# Main.net
KiCad netlist of a schematic drawn in Altium Designer
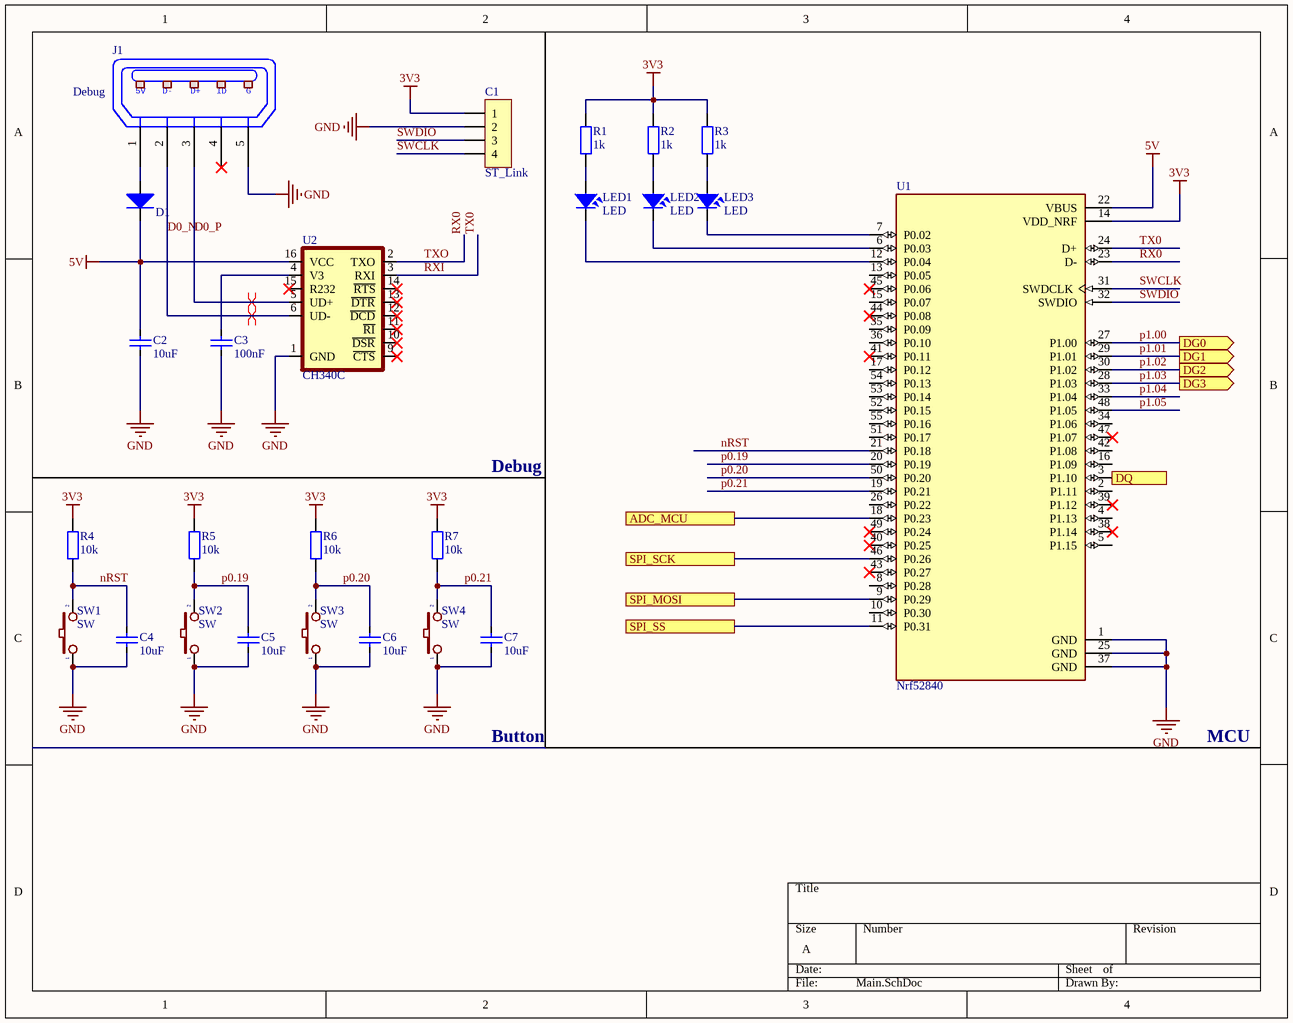
[diagram p0: Main.SchDoc]

(export (version "E")
  (design (tool "Eeschema 10.0.6"))
  (components
    (comp (ref "C1")
      (value "ST_Link")
      (footprint "J4-D1T")
      (description "WR-PHD 2.00 mm Socket Header")
      (fields
        (field (name "MANUFACTURER") "Würth Elektronik eiSos GmbH")
        (field (name "PARTNO") "62000411821")
        (field (name "CREATED BY") "Karrer Zheng")
      )
      (libsource (lib "Main") (part "JP4x1-2.0"))
    )
    (comp (ref "C2")
      (value "10uF")
      (footprint "CAP_0805")
      (description "Capacitor")
      (fields (field (name "PUBLISHER") "Altium Limited"))
      (libsource (lib "My Library") (part "CapSMD"))
    )
    (comp (ref "C3")
      (value "100nF")
      (footprint "CAP_0805")
      (description "Capacitor")
      (fields (field (name "PUBLISHER") "Altium Limited"))
      (libsource (lib "My Library") (part "CapSMD"))
    )
    (comp (ref "C4")
      (value "10uF")
      (footprint "CAP_0805")
      (description "Capacitor")
      (fields (field (name "PUBLISHER") "Altium Limited"))
      (libsource (lib "My Library") (part "CapSMD"))
    )
    (comp (ref "C5")
      (value "10uF")
      (footprint "CAP_0805")
      (description "Capacitor")
      (fields (field (name "PUBLISHER") "Altium Limited"))
      (libsource (lib "My Library") (part "CapSMD"))
    )
    (comp (ref "C6")
      (value "10uF")
      (footprint "CAP_0805")
      (description "Capacitor")
      (fields (field (name "PUBLISHER") "Altium Limited"))
      (libsource (lib "My Library") (part "CapSMD"))
    )
    (comp (ref "C7")
      (value "10uF")
      (footprint "CAP_0805")
      (description "Capacitor")
      (fields (field (name "PUBLISHER") "Altium Limited"))
      (libsource (lib "My Library") (part "CapSMD"))
    )
    (comp (ref "D1")
      (value "Diode SMD")
      (footprint "DIO-214AC(SMA)")
      (description "Default Diode")
      (fields (field (name "PUBLISHER") "Altium Limited"))
      (libsource (lib "My Library") (part "Diode SMD"))
    )
    (comp (ref "J1")
      (value "Debug")
      (footprint "USB-M1")
      (fields
        (field (name "MANUFACTURER") "FCI")
        (field (name "MANUFACTURER PART NUMBER") "10118193-0001LF")
        (field (name ".CREATOR") "MM")
        (field (name ".CHECKED PCB") "RF")
        (field (name ".CHECKED SCH") "MM")
      )
      (libsource (lib "My Library") (part "USB-5"))
    )
    (comp (ref "LED1")
      (value "LED")
      (footprint "LED-0805-Red")
      (description "LED Single colour Green and Red")
      (libsource (lib "My Library") (part "LED"))
    )
    (comp (ref "LED2")
      (value "LED")
      (footprint "LED-0805-Yellow")
      (description "LED Single colour Green and Red")
      (libsource (lib "My Library") (part "LED"))
    )
    (comp (ref "LED3")
      (value "LED")
      (footprint "LED-0805-Green")
      (description "LED Single colour Green and Red")
      (libsource (lib "My Library") (part "LED"))
    )
    (comp (ref "R1")
      (value "1k")
      (footprint "RES-SMD-0805")
      (description "Resistor SMD")
      (fields
        (field (name "MANUFACTURER") "Generic Components")
        (field (name "PUBLISHER") "Altium Hobart Technology Centre")
      )
      (libsource (lib "My Library") (part "Resistor - SMD"))
    )
    (comp (ref "R2")
      (value "1k")
      (footprint "RES-SMD-0805")
      (description "Resistor SMD")
      (fields
        (field (name "MANUFACTURER") "Generic Components")
        (field (name "PUBLISHER") "Altium Hobart Technology Centre")
      )
      (libsource (lib "My Library") (part "Resistor - SMD"))
    )
    (comp (ref "R3")
      (value "1k")
      (footprint "RES-SMD-0805")
      (description "Resistor SMD")
      (fields
        (field (name "MANUFACTURER") "Generic Components")
        (field (name "PUBLISHER") "Altium Hobart Technology Centre")
      )
      (libsource (lib "My Library") (part "Resistor - SMD"))
    )
    (comp (ref "R4")
      (value "10k")
      (footprint "RES-SMD-0805")
      (description "Resistor SMD")
      (fields
        (field (name "MANUFACTURER") "Generic Components")
        (field (name "PUBLISHER") "Altium Hobart Technology Centre")
      )
      (libsource (lib "My Library") (part "Resistor - SMD"))
    )
    (comp (ref "R5")
      (value "10k")
      (footprint "RES-SMD-0805")
      (description "Resistor SMD")
      (fields
        (field (name "MANUFACTURER") "Generic Components")
        (field (name "PUBLISHER") "Altium Hobart Technology Centre")
      )
      (libsource (lib "My Library") (part "Resistor - SMD"))
    )
    (comp (ref "R6")
      (value "10k")
      (footprint "RES-SMD-0805")
      (description "Resistor SMD")
      (fields
        (field (name "MANUFACTURER") "Generic Components")
        (field (name "PUBLISHER") "Altium Hobart Technology Centre")
      )
      (libsource (lib "My Library") (part "Resistor - SMD"))
    )
    (comp (ref "R7")
      (value "10k")
      (footprint "RES-SMD-0805")
      (description "Resistor SMD")
      (fields
        (field (name "MANUFACTURER") "Generic Components")
        (field (name "PUBLISHER") "Altium Hobart Technology Centre")
      )
      (libsource (lib "My Library") (part "Resistor - SMD"))
    )
    (comp (ref "SW1")
      (value "SW")
      (footprint "SW 3x2x4")
      (description "Switch button 2 pin")
      (libsource (lib "My Library") (part "SW2"))
    )
    (comp (ref "SW2")
      (value "SW")
      (footprint "SW2")
      (description "Switch button 2 pin")
      (libsource (lib "My Library") (part "SW2"))
    )
    (comp (ref "SW3")
      (value "SW")
      (footprint "SW2")
      (description "Switch button 2 pin")
      (libsource (lib "My Library") (part "SW2"))
    )
    (comp (ref "SW4")
      (value "SW")
      (footprint "SW2")
      (description "Switch button 2 pin")
      (libsource (lib "My Library") (part "SW2"))
    )
    (comp (ref "U1")
      (value "Nrf52840")
      (footprint "NRF52840")
      (description "Module SoC")
      (libsource (lib "Main") (part "Nrf52840"))
    )
    (comp (ref "U2")
      (value "CH340C")
      (footprint "SOP-16")
      (description "USB to serial chip CH340")
      (fields (field (name "MF") "WCH"))
      (libsource (lib "My Library") (part "CH340C"))
    )
  )
  (nets
    (net (code "1") (name "/ADC_MCU") (class "Default")
      (node (ref "U1") (pin "18") (pinfunction "P0.23_18") (pintype "bidirectional"))
    )
    (net (code "2") (name "/D0_N") (class "Default")
      (node (ref "J1") (pin "2") (pinfunction "P2_2") (pintype "passive"))
      (node (ref "U2") (pin "6") (pinfunction "UD-_6") (pintype "bidirectional"))
    )
    (net (code "3") (name "/D0_P") (class "Default")
      (node (ref "J1") (pin "3") (pinfunction "P3_3") (pintype "passive"))
      (node (ref "U2") (pin "5") (pinfunction "UD+_5") (pintype "bidirectional"))
    )
    (net (code "4") (name "/DQ") (class "Default")
      (node (ref "U1") (pin "3") (pinfunction "P1.10_3") (pintype "bidirectional"))
    )
    (net (code "5") (name "/RX0") (class "Default")
      (node (ref "U1") (pin "23") (pinfunction "D-_23") (pintype "bidirectional"))
      (node (ref "U2") (pin "2") (pinfunction "TXO_2") (pintype "bidirectional"))
    )
    (net (code "6") (name "/RXI") (class "Default")
      (node (ref "U1") (pin "24") (pinfunction "D+_24") (pintype "bidirectional"))
      (node (ref "U2") (pin "3") (pinfunction "RXI_3") (pintype "bidirectional"))
    )
    (net (code "7") (name "/SPI_MOSI") (class "Default")
      (node (ref "U1") (pin "9") (pinfunction "P0.29_9") (pintype "bidirectional"))
    )
    (net (code "8") (name "/SPI_SCK") (class "Default")
      (node (ref "U1") (pin "46") (pinfunction "P0.26_46") (pintype "bidirectional"))
    )
    (net (code "9") (name "/SPI_SS") (class "Default")
      (node (ref "U1") (pin "11") (pinfunction "P0.31_11") (pintype "bidirectional"))
    )
    (net (code "10") (name "/SWCLK") (class "Default")
      (node (ref "C1") (pin "4") (pinfunction "4_4") (pintype "passive"))
      (node (ref "U1") (pin "31") (pinfunction "SWDCLK_31") (pintype "input"))
    )
    (net (code "11") (name "/SWDIO") (class "Default")
      (node (ref "C1") (pin "3") (pinfunction "3_3") (pintype "passive"))
      (node (ref "U1") (pin "32") (pinfunction "SWDIO_32") (pintype "input"))
    )
    (net (code "12") (name "/nRST") (class "Default")
      (node (ref "C4") (pin "2") (pinfunction "2_2") (pintype "passive"))
      (node (ref "R4") (pin "2") (pinfunction "2_2") (pintype "passive"))
      (node (ref "SW1") (pin "2") (pinfunction "2_2") (pintype "passive"))
      (node (ref "U1") (pin "21") (pinfunction "P0.18_21") (pintype "bidirectional"))
    )
    (net (code "13") (name "/p0.19") (class "Default")
      (node (ref "C5") (pin "2") (pinfunction "2_2") (pintype "passive"))
      (node (ref "R5") (pin "2") (pinfunction "2_2") (pintype "passive"))
      (node (ref "SW2") (pin "2") (pinfunction "2_2") (pintype "passive"))
      (node (ref "U1") (pin "20") (pinfunction "P0.19_20") (pintype "bidirectional"))
    )
    (net (code "14") (name "/p0.20") (class "Default")
      (node (ref "C6") (pin "2") (pinfunction "2_2") (pintype "passive"))
      (node (ref "R6") (pin "2") (pinfunction "2_2") (pintype "passive"))
      (node (ref "SW3") (pin "2") (pinfunction "2_2") (pintype "passive"))
      (node (ref "U1") (pin "50") (pinfunction "P0.20_50") (pintype "bidirectional"))
    )
    (net (code "15") (name "/p0.21") (class "Default")
      (node (ref "C7") (pin "2") (pinfunction "2_2") (pintype "passive"))
      (node (ref "R7") (pin "2") (pinfunction "2_2") (pintype "passive"))
      (node (ref "SW4") (pin "2") (pinfunction "2_2") (pintype "passive"))
      (node (ref "U1") (pin "19") (pinfunction "P0.21_19") (pintype "bidirectional"))
    )
    (net (code "16") (name "/p1.00") (class "Default")
      (node (ref "U1") (pin "27") (pinfunction "P1.00_27") (pintype "bidirectional"))
    )
    (net (code "17") (name "/p1.01") (class "Default")
      (node (ref "U1") (pin "29") (pinfunction "P1.01_29") (pintype "bidirectional"))
    )
    (net (code "18") (name "/p1.02") (class "Default")
      (node (ref "U1") (pin "30") (pinfunction "P1.02_30") (pintype "bidirectional"))
    )
    (net (code "19") (name "/p1.03") (class "Default")
      (node (ref "U1") (pin "28") (pinfunction "P1.03_28") (pintype "bidirectional"))
    )
    (net (code "20") (name "/p1.04") (class "Default")
      (node (ref "U1") (pin "33") (pinfunction "P1.04_33") (pintype "bidirectional"))
    )
    (net (code "21") (name "/p1.05") (class "Default")
      (node (ref "U1") (pin "48") (pinfunction "P1.05_48") (pintype "bidirectional"))
    )
    (net (code "22") (name "3V3") (class "Default")
      (node (ref "C1") (pin "1") (pinfunction "1_1") (pintype "passive"))
      (node (ref "R1") (pin "1") (pinfunction "1_1") (pintype "passive"))
      (node (ref "R2") (pin "1") (pinfunction "1_1") (pintype "passive"))
      (node (ref "R3") (pin "1") (pinfunction "1_1") (pintype "passive"))
      (node (ref "R4") (pin "1") (pinfunction "1_1") (pintype "passive"))
      (node (ref "R5") (pin "1") (pinfunction "1_1") (pintype "passive"))
      (node (ref "R6") (pin "1") (pinfunction "1_1") (pintype "passive"))
      (node (ref "R7") (pin "1") (pinfunction "1_1") (pintype "passive"))
      (node (ref "U1") (pin "14") (pinfunction "VDD_NRF_14") (pintype "power_in"))
    )
    (net (code "23") (name "5V") (class "Default")
      (node (ref "C2") (pin "2") (pinfunction "2_2") (pintype "passive"))
      (node (ref "D1") (pin "2") (pinfunction "K_2") (pintype "passive"))
      (node (ref "U1") (pin "22") (pinfunction "VBUS_22") (pintype "power_in"))
      (node (ref "U2") (pin "16") (pinfunction "VCC_16") (pintype "bidirectional"))
    )
    (net (code "24") (name "GND") (class "Default")
      (node (ref "C1") (pin "2") (pinfunction "2_2") (pintype "passive"))
      (node (ref "C2") (pin "1") (pinfunction "1_1") (pintype "passive"))
      (node (ref "C3") (pin "1") (pinfunction "1_1") (pintype "passive"))
      (node (ref "C4") (pin "1") (pinfunction "1_1") (pintype "passive"))
      (node (ref "C5") (pin "1") (pinfunction "1_1") (pintype "passive"))
      (node (ref "C6") (pin "1") (pinfunction "1_1") (pintype "passive"))
      (node (ref "C7") (pin "1") (pinfunction "1_1") (pintype "passive"))
      (node (ref "J1") (pin "5") (pinfunction "P5_5") (pintype "passive"))
      (node (ref "SW1") (pin "1") (pinfunction "1_1") (pintype "passive"))
      (node (ref "SW2") (pin "1") (pinfunction "1_1") (pintype "passive"))
      (node (ref "SW3") (pin "1") (pinfunction "1_1") (pintype "passive"))
      (node (ref "SW4") (pin "1") (pinfunction "1_1") (pintype "passive"))
      (node (ref "U1") (pin "1") (pinfunction "GND_1") (pintype "power_in"))
      (node (ref "U1") (pin "25") (pinfunction "GND_25") (pintype "power_in"))
      (node (ref "U1") (pin "37") (pinfunction "GND_37") (pintype "power_in"))
      (node (ref "U2") (pin "1") (pinfunction "GND_1") (pintype "bidirectional"))
    )
    (net (code "25") (name "Net-(D1-A)") (class "Default")
      (node (ref "D1") (pin "1") (pinfunction "A_1") (pintype "passive"))
      (node (ref "J1") (pin "1") (pinfunction "P1_1") (pintype "passive"))
    )
    (net (code "26") (name "Net-(LED1-Pad1)") (class "Default")
      (node (ref "LED1") (pin "1") (pinfunction "1_1") (pintype "passive"))
      (node (ref "R1") (pin "2") (pinfunction "2_2") (pintype "passive"))
    )
    (net (code "27") (name "Net-(LED2-Pad1)") (class "Default")
      (node (ref "LED2") (pin "1") (pinfunction "1_1") (pintype "passive"))
      (node (ref "R2") (pin "2") (pinfunction "2_2") (pintype "passive"))
    )
    (net (code "28") (name "Net-(LED3-Pad1)") (class "Default")
      (node (ref "LED3") (pin "1") (pinfunction "1_1") (pintype "passive"))
      (node (ref "R3") (pin "2") (pinfunction "2_2") (pintype "passive"))
    )
    (net (code "29") (name "Net-(U1-P0.02)") (class "Default")
      (node (ref "LED3") (pin "2") (pinfunction "2_2") (pintype "passive"))
      (node (ref "U1") (pin "7") (pinfunction "P0.02_7") (pintype "bidirectional"))
    )
    (net (code "30") (name "Net-(U1-P0.03)") (class "Default")
      (node (ref "LED2") (pin "2") (pinfunction "2_2") (pintype "passive"))
      (node (ref "U1") (pin "6") (pinfunction "P0.03_6") (pintype "bidirectional"))
    )
    (net (code "31") (name "Net-(U1-P0.04)") (class "Default")
      (node (ref "LED1") (pin "2") (pinfunction "2_2") (pintype "passive"))
      (node (ref "U1") (pin "12") (pinfunction "P0.04_12") (pintype "bidirectional"))
    )
    (net (code "32") (name "Net-(U2-V3)") (class "Default")
      (node (ref "C3") (pin "2") (pinfunction "2_2") (pintype "passive"))
      (node (ref "U2") (pin "4") (pinfunction "V3_4") (pintype "bidirectional"))
    )
    (net (code "33") (name "unconnected-(J1-P4-Pad4)") (class "Default")
      (node (ref "J1") (pin "4") (pinfunction "P4_4") (pintype "passive+no_connect"))
    )
    (net (code "34") (name "unconnected-(U1-P0.05-Pad13)") (class "Default")
      (node (ref "U1") (pin "13") (pinfunction "P0.05_13") (pintype "bidirectional"))
    )
    (net (code "35") (name "unconnected-(U1-P0.06-Pad45)") (class "Default")
      (node (ref "U1") (pin "45") (pinfunction "P0.06_45") (pintype "bidirectional+no_connect"))
    )
    (net (code "36") (name "unconnected-(U1-P0.07-Pad15)") (class "Default")
      (node (ref "U1") (pin "15") (pinfunction "P0.07_15") (pintype "bidirectional"))
    )
    (net (code "37") (name "unconnected-(U1-P0.08-Pad44)") (class "Default")
      (node (ref "U1") (pin "44") (pinfunction "P0.08_44") (pintype "bidirectional+no_connect"))
    )
    (net (code "38") (name "unconnected-(U1-P0.09-Pad35)") (class "Default")
      (node (ref "U1") (pin "35") (pinfunction "P0.09_35") (pintype "bidirectional"))
    )
    (net (code "39") (name "unconnected-(U1-P0.10-Pad36)") (class "Default")
      (node (ref "U1") (pin "36") (pinfunction "P0.10_36") (pintype "bidirectional"))
    )
    (net (code "40") (name "unconnected-(U1-P0.11-Pad41)") (class "Default")
      (node (ref "U1") (pin "41") (pinfunction "P0.11_41") (pintype "bidirectional+no_connect"))
    )
    (net (code "41") (name "unconnected-(U1-P0.12-Pad17)") (class "Default")
      (node (ref "U1") (pin "17") (pinfunction "P0.12_17") (pintype "bidirectional"))
    )
    (net (code "42") (name "unconnected-(U1-P0.13-Pad54)") (class "Default")
      (node (ref "U1") (pin "54") (pinfunction "P0.13_54") (pintype "bidirectional"))
    )
    (net (code "43") (name "unconnected-(U1-P0.14-Pad53)") (class "Default")
      (node (ref "U1") (pin "53") (pinfunction "P0.14_53") (pintype "bidirectional"))
    )
    (net (code "44") (name "unconnected-(U1-P0.15-Pad52)") (class "Default")
      (node (ref "U1") (pin "52") (pinfunction "P0.15_52") (pintype "bidirectional"))
    )
    (net (code "45") (name "unconnected-(U1-P0.16-Pad55)") (class "Default")
      (node (ref "U1") (pin "55") (pinfunction "P0.16_55") (pintype "bidirectional"))
    )
    (net (code "46") (name "unconnected-(U1-P0.17-Pad51)") (class "Default")
      (node (ref "U1") (pin "51") (pinfunction "P0.17_51") (pintype "bidirectional"))
    )
    (net (code "47") (name "unconnected-(U1-P0.22-Pad26)") (class "Default")
      (node (ref "U1") (pin "26") (pinfunction "P0.22_26") (pintype "bidirectional"))
    )
    (net (code "48") (name "unconnected-(U1-P0.24-Pad49)") (class "Default")
      (node (ref "U1") (pin "49") (pinfunction "P0.24_49") (pintype "bidirectional+no_connect"))
    )
    (net (code "49") (name "unconnected-(U1-P0.25-Pad40)") (class "Default")
      (node (ref "U1") (pin "40") (pinfunction "P0.25_40") (pintype "bidirectional+no_connect"))
    )
    (net (code "50") (name "unconnected-(U1-P0.27-Pad43)") (class "Default")
      (node (ref "U1") (pin "43") (pinfunction "P0.27_43") (pintype "bidirectional+no_connect"))
    )
    (net (code "51") (name "unconnected-(U1-P0.28-Pad8)") (class "Default")
      (node (ref "U1") (pin "8") (pinfunction "P0.28_8") (pintype "bidirectional"))
    )
    (net (code "52") (name "unconnected-(U1-P0.30-Pad10)") (class "Default")
      (node (ref "U1") (pin "10") (pinfunction "P0.30_10") (pintype "bidirectional"))
    )
    (net (code "53") (name "unconnected-(U1-P1.06-Pad34)") (class "Default")
      (node (ref "U1") (pin "34") (pinfunction "P1.06_34") (pintype "bidirectional"))
    )
    (net (code "54") (name "unconnected-(U1-P1.07-Pad47)") (class "Default")
      (node (ref "U1") (pin "47") (pinfunction "P1.07_47") (pintype "bidirectional+no_connect"))
    )
    (net (code "55") (name "unconnected-(U1-P1.08-Pad42)") (class "Default")
      (node (ref "U1") (pin "42") (pinfunction "P1.08_42") (pintype "bidirectional"))
    )
    (net (code "56") (name "unconnected-(U1-P1.09-Pad16)") (class "Default")
      (node (ref "U1") (pin "16") (pinfunction "P1.09_16") (pintype "bidirectional"))
    )
    (net (code "57") (name "unconnected-(U1-P1.11-Pad2)") (class "Default")
      (node (ref "U1") (pin "2") (pinfunction "P1.11_2") (pintype "bidirectional"))
    )
    (net (code "58") (name "unconnected-(U1-P1.12-Pad39)") (class "Default")
      (node (ref "U1") (pin "39") (pinfunction "P1.12_39") (pintype "bidirectional+no_connect"))
    )
    (net (code "59") (name "unconnected-(U1-P1.13-Pad4)") (class "Default")
      (node (ref "U1") (pin "4") (pinfunction "P1.13_4") (pintype "bidirectional"))
    )
    (net (code "60") (name "unconnected-(U1-P1.14-Pad38)") (class "Default")
      (node (ref "U1") (pin "38") (pinfunction "P1.14_38") (pintype "bidirectional+no_connect"))
    )
    (net (code "61") (name "unconnected-(U1-P1.15-Pad5)") (class "Default")
      (node (ref "U1") (pin "5") (pinfunction "P1.15_5") (pintype "bidirectional"))
    )
    (net (code "62") (name "unconnected-(U2-R232-Pad15)") (class "Default")
      (node (ref "U2") (pin "15") (pinfunction "R232_15") (pintype "bidirectional+no_connect"))
    )
    (net (code "63") (name "unconnected-(U2-~{CTS}-Pad9)") (class "Default")
      (node (ref "U2") (pin "9") (pinfunction "~{CTS}_9") (pintype "bidirectional+no_connect"))
    )
    (net (code "64") (name "unconnected-(U2-~{DCD}-Pad12)") (class "Default")
      (node (ref "U2") (pin "12") (pinfunction "~{DCD}_12") (pintype "bidirectional+no_connect"))
    )
    (net (code "65") (name "unconnected-(U2-~{DSR}-Pad10)") (class "Default")
      (node (ref "U2") (pin "10") (pinfunction "~{DSR}_10") (pintype "bidirectional+no_connect"))
    )
    (net (code "66") (name "unconnected-(U2-~{DTR}-Pad13)") (class "Default")
      (node (ref "U2") (pin "13") (pinfunction "~{DTR}_13") (pintype "bidirectional+no_connect"))
    )
    (net (code "67") (name "unconnected-(U2-~{RI}-Pad11)") (class "Default")
      (node (ref "U2") (pin "11") (pinfunction "~{RI}_11") (pintype "bidirectional+no_connect"))
    )
    (net (code "68") (name "unconnected-(U2-~{RTS}-Pad14)") (class "Default")
      (node (ref "U2") (pin "14") (pinfunction "~{RTS}_14") (pintype "bidirectional+no_connect"))
    )
  )
)
